# TXB0108_Voltage_Level_Translator.net
KiCad netlist of a schematic drawn in Altium Designer
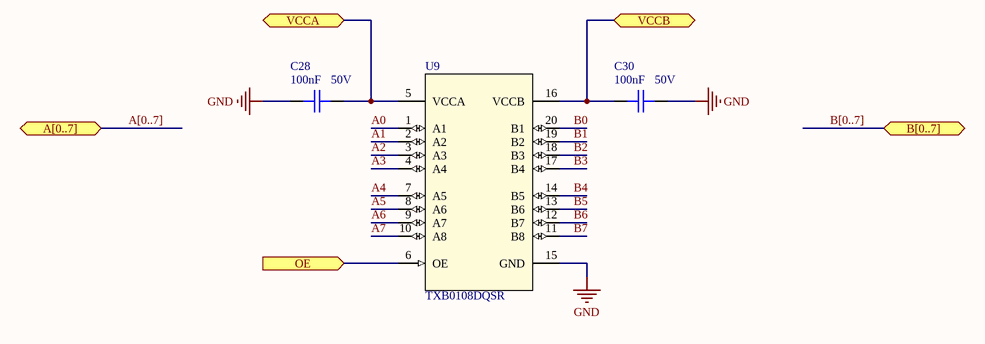
[diagram p0: TXB0108 Voltage_Level_Translator.SchDoc]

(export (version "E")
  (design (tool "Eeschema 10.0.6"))
  (components
    (comp (ref "C28")
      (value "CAP CER 0.1UF 50V X7R 0402")
      (footprint "C0402")
      (description "0.1µF ±10% 50V Ceramic Capacitor X7R 0402 (1005 Metric)")
      (fields
        (field (name "MANUFACTURER") "TDK")
        (field (name "MANUFACTURER PART NUMBER") "CGA2B3X7R1H104K050BB")
        (field (name "CAPACITANCE") "100nF")
        (field (name "VOLTAGE") "50V")
      )
      (libsource (lib "capacitors_smd") (part "CAP CER 0.1UF 50V X7R 0402"))
    )
    (comp (ref "C30")
      (value "CAP CER 0.1UF 50V X7R 0402")
      (footprint "C0402")
      (description "0.1µF ±10% 50V Ceramic Capacitor X7R 0402 (1005 Metric)")
      (fields
        (field (name "MANUFACTURER") "TDK")
        (field (name "MANUFACTURER PART NUMBER") "CGA2B3X7R1H104K050BB")
        (field (name "CAPACITANCE") "100nF")
        (field (name "VOLTAGE") "50V")
      )
      (libsource (lib "capacitors_smd") (part "CAP CER 0.1UF 50V X7R 0402"))
    )
    (comp (ref "U9")
      (value "TXB0108DQSR")
      (footprint "DQS20_TEX")
      (description "Voltage Level Translator Bidirectional 1 Circuit 8 Channel 100Mbps 20-USON (4x2)")
      (fields (field (name "MANUFACTURER") "Texas Instruments"))
      (libsource (lib "BLDC_Motor_Driver") (part "IC TXB0108 TRNSLTR BIDIRECTIONAL 20USON"))
    )
  )
  (nets
    (net (code "1") (name "/A0") (class "Default")
      (node (ref "U9") (pin "1") (pinfunction "A1_1") (pintype "bidirectional"))
    )
    (net (code "2") (name "/A1") (class "Default")
      (node (ref "U9") (pin "2") (pinfunction "A2_2") (pintype "bidirectional"))
    )
    (net (code "3") (name "/A2") (class "Default")
      (node (ref "U9") (pin "3") (pinfunction "A3_3") (pintype "bidirectional"))
    )
    (net (code "4") (name "/A3") (class "Default")
      (node (ref "U9") (pin "4") (pinfunction "A4_4") (pintype "bidirectional"))
    )
    (net (code "5") (name "/A4") (class "Default")
      (node (ref "U9") (pin "7") (pinfunction "A5_7") (pintype "bidirectional"))
    )
    (net (code "6") (name "/A5") (class "Default")
      (node (ref "U9") (pin "8") (pinfunction "A6_8") (pintype "bidirectional"))
    )
    (net (code "7") (name "/A6") (class "Default")
      (node (ref "U9") (pin "9") (pinfunction "A7_9") (pintype "bidirectional"))
    )
    (net (code "8") (name "/A7") (class "Default")
      (node (ref "U9") (pin "10") (pinfunction "A8_10") (pintype "bidirectional"))
    )
    (net (code "10") (name "/B0") (class "Default")
      (node (ref "U9") (pin "20") (pinfunction "B1_20") (pintype "bidirectional"))
    )
    (net (code "11") (name "/B1") (class "Default")
      (node (ref "U9") (pin "19") (pinfunction "B2_19") (pintype "bidirectional"))
    )
    (net (code "12") (name "/B2") (class "Default")
      (node (ref "U9") (pin "18") (pinfunction "B3_18") (pintype "bidirectional"))
    )
    (net (code "13") (name "/B3") (class "Default")
      (node (ref "U9") (pin "17") (pinfunction "B4_17") (pintype "bidirectional"))
    )
    (net (code "14") (name "/B4") (class "Default")
      (node (ref "U9") (pin "14") (pinfunction "B5_14") (pintype "bidirectional"))
    )
    (net (code "15") (name "/B5") (class "Default")
      (node (ref "U9") (pin "13") (pinfunction "B6_13") (pintype "bidirectional"))
    )
    (net (code "16") (name "/B6") (class "Default")
      (node (ref "U9") (pin "12") (pinfunction "B7_12") (pintype "bidirectional"))
    )
    (net (code "17") (name "/B7") (class "Default")
      (node (ref "U9") (pin "11") (pinfunction "B8_11") (pintype "bidirectional"))
    )
    (net (code "19") (name "/OE") (class "Default")
      (node (ref "U9") (pin "6") (pinfunction "OE_6") (pintype "input"))
    )
    (net (code "20") (name "/VCCA") (class "Default")
      (node (ref "C28") (pin "2") (pinfunction "2_2") (pintype "passive"))
      (node (ref "U9") (pin "5") (pinfunction "VCCA_5") (pintype "power_in"))
    )
    (net (code "21") (name "/VCCB") (class "Default")
      (node (ref "C30") (pin "1") (pinfunction "1_1") (pintype "passive"))
      (node (ref "U9") (pin "16") (pinfunction "VCCB_16") (pintype "power_in"))
    )
    (net (code "22") (name "GND") (class "Default")
      (node (ref "C28") (pin "1") (pinfunction "1_1") (pintype "passive"))
      (node (ref "C30") (pin "2") (pinfunction "2_2") (pintype "passive"))
      (node (ref "U9") (pin "15") (pinfunction "GND_15") (pintype "power_in"))
    )
  )
)
